# tes1.net
KiCad netlist of a schematic drawn in EAGLE
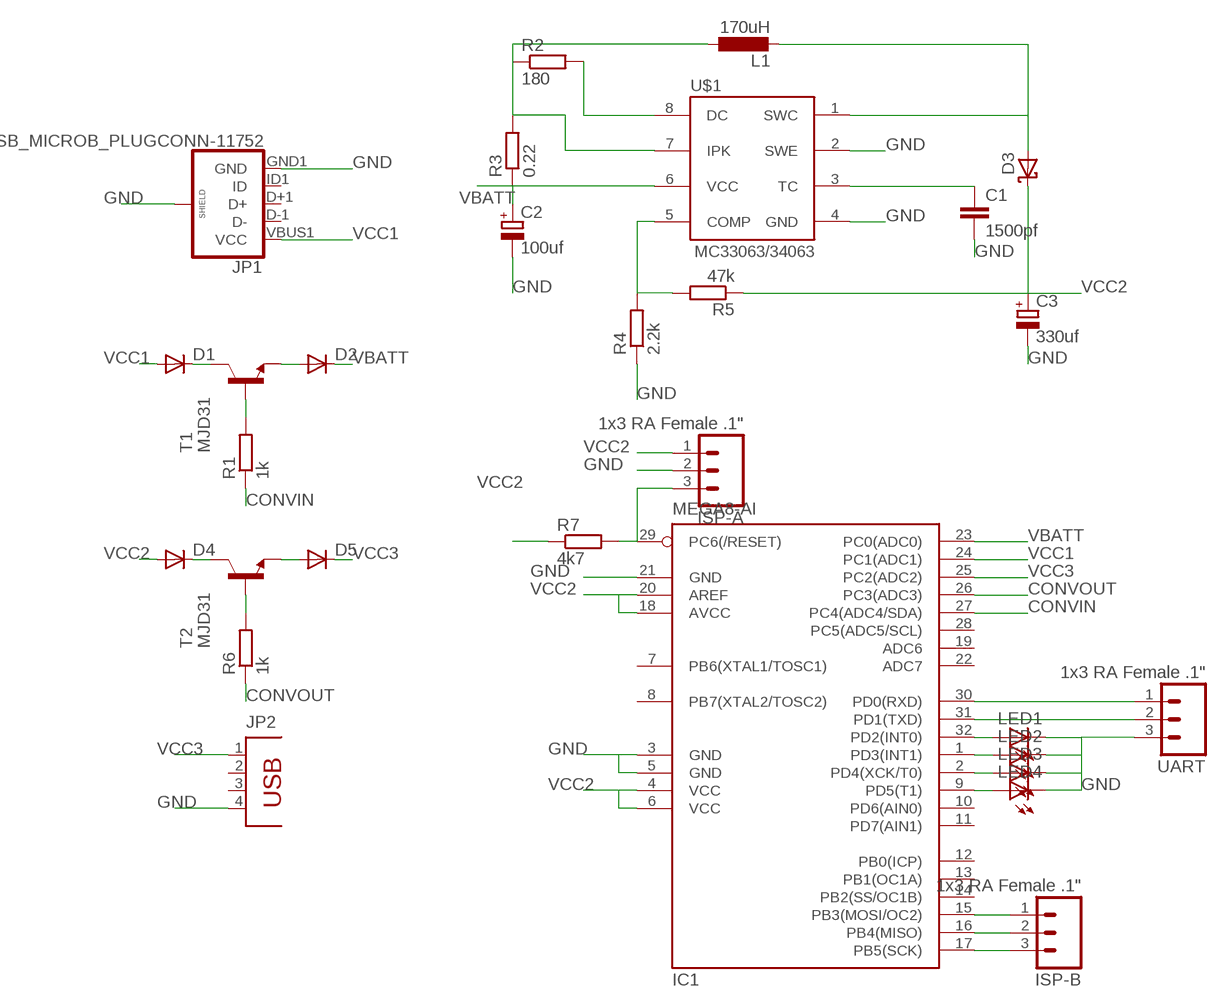
[diagram p0: schematic, sheet 1]

(export (version "E")
  (design (tool "Eeschema 10.0.6"))
  (components
    (comp (ref "C1")
      (value "1500pf")
      (footprint "eagle-import:C1206")
      (libsource (lib "eagle-import") (part "C-EUC1206"))
    )
    (comp (ref "C2")
      (value "100uf")
      (footprint "eagle-import:153CLV-1014")
      (libsource (lib "eagle-import") (part "CPOL-EU153CLV-1014"))
    )
    (comp (ref "C3")
      (value "330uf")
      (footprint "eagle-import:153CLV-1014")
      (libsource (lib "eagle-import") (part "CPOL-EU153CLV-1014"))
    )
    (comp (ref "D1")
      (value "DIODE-SMC")
      (footprint "eagle-import:SMC")
      (libsource (lib "eagle-import") (part "DIODE-SMC"))
    )
    (comp (ref "D2")
      (value "DIODE-SMC")
      (footprint "eagle-import:SMC")
      (libsource (lib "eagle-import") (part "DIODE-SMC"))
    )
    (comp (ref "D3")
      (value "SCHOTTKY-DIODEF126Z12")
      (footprint "eagle-import:F126Z12")
      (libsource (lib "eagle-import") (part "SCHOTTKY-DIODEF126Z12"))
    )
    (comp (ref "D4")
      (value "DIODE-SMC")
      (footprint "eagle-import:SMC")
      (libsource (lib "eagle-import") (part "DIODE-SMC"))
    )
    (comp (ref "D5")
      (value "DIODE-SMC")
      (footprint "eagle-import:SMC")
      (libsource (lib "eagle-import") (part "DIODE-SMC"))
    )
    (comp (ref "IC1")
      (value "MEGA8-AI")
      (footprint "eagle-import:TQFP32-08")
      (fields (field (name "MPN") "ATMEGA8-16AU"))
      (libsource (lib "eagle-import") (part "MEGA8-AI"))
    )
    (comp (ref "ISP-A")
      (value "1x3 RA Female .1\"")
      (footprint "eagle-import:1X03_SMD_RA_FEMALE")
      (libsource (lib "eagle-import") (part "M03SMD_RA_FEMALE"))
    )
    (comp (ref "ISP-B")
      (value "1x3 RA Female .1\"")
      (footprint "eagle-import:1X03_SMD_RA_FEMALE")
      (libsource (lib "eagle-import") (part "M03SMD_RA_FEMALE"))
    )
    (comp (ref "JP1")
      (value "USB_MICROB_PLUGCONN-11752")
      (footprint "eagle-import:USB-B-MICRO-SMD_V03")
      (libsource (lib "eagle-import") (part "USB_MICROB_PLUGCONN-11752"))
    )
    (comp (ref "JP2")
      (value "PN87520")
      (footprint "eagle-import:PN87520")
      (libsource (lib "eagle-import") (part "PN87520"))
    )
    (comp (ref "L1")
      (value "170uH")
      (footprint "eagle-import:L5650M")
      (libsource (lib "eagle-import") (part "L-EUL5650M"))
    )
    (comp (ref "LED1")
      (value "LEDSML1206")
      (footprint "eagle-import:SML1206")
      (libsource (lib "eagle-import") (part "LEDSML1206"))
    )
    (comp (ref "LED2")
      (value "LEDSML1206")
      (footprint "eagle-import:SML1206")
      (libsource (lib "eagle-import") (part "LEDSML1206"))
    )
    (comp (ref "LED3")
      (value "LEDSML1206")
      (footprint "eagle-import:SML1206")
      (libsource (lib "eagle-import") (part "LEDSML1206"))
    )
    (comp (ref "LED4")
      (value "LEDSML1206")
      (footprint "eagle-import:SML1206")
      (libsource (lib "eagle-import") (part "LEDSML1206"))
    )
    (comp (ref "R1")
      (value "1k")
      (footprint "eagle-import:R1206")
      (libsource (lib "eagle-import") (part "R-EU_R1206"))
    )
    (comp (ref "R2")
      (value "180")
      (footprint "eagle-import:R1206")
      (libsource (lib "eagle-import") (part "resistor_R-EU_R1206"))
    )
    (comp (ref "R3")
      (value "0.22")
      (footprint "eagle-import:R1206")
      (libsource (lib "eagle-import") (part "resistor_R-EU_R1206"))
    )
    (comp (ref "R4")
      (value "2.2k")
      (footprint "eagle-import:R1206")
      (libsource (lib "eagle-import") (part "resistor_R-EU_R1206"))
    )
    (comp (ref "R5")
      (value "47k")
      (footprint "eagle-import:R1206")
      (libsource (lib "eagle-import") (part "resistor_R-EU_R1206"))
    )
    (comp (ref "R6")
      (value "1k")
      (footprint "eagle-import:R1206")
      (libsource (lib "eagle-import") (part "R-EU_R1206"))
    )
    (comp (ref "R7")
      (value "4k7")
      (footprint "eagle-import:R1206")
      (libsource (lib "eagle-import") (part "R-EU_R1206"))
    )
    (comp (ref "T1")
      (value "MJD31")
      (footprint "eagle-import:DPAK")
      (libsource (lib "eagle-import") (part "MJD31"))
    )
    (comp (ref "T2")
      (value "MJD31")
      (footprint "eagle-import:DPAK")
      (libsource (lib "eagle-import") (part "MJD31"))
    )
    (comp (ref "U$1")
      (value "MC33063/MC34063D")
      (footprint "eagle-import:SO08")
      (libsource (lib "eagle-import") (part "MC33063/MC34063D"))
    )
    (comp (ref "UART")
      (value "1x3 RA Female .1\"")
      (footprint "eagle-import:1X03_SMD_RA_FEMALE")
      (libsource (lib "eagle-import") (part "M03SMD_RA_FEMALE"))
    )
  )
  (nets
    (net (code "1") (name "/CONVIN") (class "Default")
      (node (ref "IC1") (pin "27") (pinfunction "PC4(ADC4/SDA)_27") (pintype "bidirectional"))
      (node (ref "R1") (pin "1") (pinfunction "1_1") (pintype "passive"))
    )
    (net (code "2") (name "/CONVOUT") (class "Default")
      (node (ref "IC1") (pin "26") (pinfunction "PC3(ADC3)_26") (pintype "bidirectional"))
      (node (ref "R6") (pin "1") (pinfunction "1_1") (pintype "passive"))
    )
    (net (code "3") (name "/GND") (class "Default")
      (node (ref "C1") (pin "2") (pinfunction "2_2") (pintype "passive"))
      (node (ref "C2") (pin "-") (pinfunction "-_-") (pintype "passive"))
      (node (ref "C3") (pin "-") (pinfunction "-_-") (pintype "passive"))
      (node (ref "IC1") (pin "21") (pinfunction "GND_21") (pintype "power_in"))
      (node (ref "IC1") (pin "3") (pinfunction "GND_3") (pintype "power_in"))
      (node (ref "IC1") (pin "5") (pinfunction "GND_5") (pintype "power_in"))
      (node (ref "ISP-A") (pin "2") (pinfunction "2_2") (pintype "passive"))
      (node (ref "JP1") (pin "GND1") (pinfunction "GND_GND1") (pintype "bidirectional"))
      (node (ref "JP1") (pin "SHIELD1") (pinfunction "SHIELD_SHIELD1") (pintype "bidirectional"))
      (node (ref "JP1") (pin "SHIELD2") (pinfunction "SHIELD_SHIELD2") (pintype "bidirectional"))
      (node (ref "JP1") (pin "SHIELD3") (pinfunction "SHIELD_SHIELD3") (pintype "bidirectional"))
      (node (ref "JP2") (pin "4") (pinfunction "4_4") (pintype "passive"))
      (node (ref "LED1") (pin "C") (pinfunction "C_C") (pintype "passive"))
      (node (ref "LED2") (pin "C") (pinfunction "C_C") (pintype "passive"))
      (node (ref "LED3") (pin "C") (pinfunction "C_C") (pintype "passive"))
      (node (ref "LED4") (pin "C") (pinfunction "C_C") (pintype "passive"))
      (node (ref "R4") (pin "1") (pinfunction "1_1") (pintype "passive"))
      (node (ref "U$1") (pin "2") (pinfunction "SWE_2") (pintype "input"))
      (node (ref "U$1") (pin "4") (pinfunction "GND_4") (pintype "power_in"))
      (node (ref "UART") (pin "3") (pinfunction "3_3") (pintype "passive"))
    )
    (net (code "4") (name "/VBATT") (class "Default")
      (node (ref "C2") (pin "+") (pinfunction "+_+") (pintype "passive"))
      (node (ref "D2") (pin "C") (pinfunction "C_C") (pintype "passive"))
      (node (ref "IC1") (pin "23") (pinfunction "PC0(ADC0)_23") (pintype "bidirectional"))
      (node (ref "R3") (pin "1") (pinfunction "1_1") (pintype "passive"))
      (node (ref "U$1") (pin "6") (pinfunction "VCC_6") (pintype "power_in"))
    )
    (net (code "5") (name "/VCC1") (class "Default")
      (node (ref "D1") (pin "A") (pinfunction "A_A") (pintype "passive"))
      (node (ref "IC1") (pin "24") (pinfunction "PC1(ADC1)_24") (pintype "bidirectional"))
      (node (ref "JP1") (pin "VBUS1") (pinfunction "VCC_VBUS1") (pintype "bidirectional"))
    )
    (net (code "6") (name "/VCC2") (class "Default")
      (node (ref "C3") (pin "+") (pinfunction "+_+") (pintype "passive"))
      (node (ref "D3") (pin "C") (pinfunction "C_C") (pintype "passive"))
      (node (ref "D4") (pin "A") (pinfunction "A_A") (pintype "passive"))
      (node (ref "IC1") (pin "18") (pinfunction "AVCC_18") (pintype "power_in"))
      (node (ref "IC1") (pin "20") (pinfunction "AREF_20") (pintype "passive"))
      (node (ref "IC1") (pin "4") (pinfunction "VCC_4") (pintype "power_in"))
      (node (ref "IC1") (pin "6") (pinfunction "VCC_6") (pintype "power_in"))
      (node (ref "ISP-A") (pin "1") (pinfunction "1_1") (pintype "passive"))
      (node (ref "R5") (pin "1") (pinfunction "1_1") (pintype "passive"))
      (node (ref "R7") (pin "1") (pinfunction "1_1") (pintype "passive"))
    )
    (net (code "7") (name "/VCC3") (class "Default")
      (node (ref "D5") (pin "C") (pinfunction "C_C") (pintype "passive"))
      (node (ref "IC1") (pin "25") (pinfunction "PC2(ADC2)_25") (pintype "bidirectional"))
      (node (ref "JP2") (pin "1") (pinfunction "1_1") (pintype "passive"))
    )
    (net (code "8") (name "Net-(IC1-PB3(MOSI{slash}OC2))") (class "Default")
      (node (ref "IC1") (pin "15") (pinfunction "PB3(MOSI/OC2)_15") (pintype "bidirectional"))
      (node (ref "ISP-B") (pin "1") (pinfunction "1_1") (pintype "passive"))
    )
    (net (code "9") (name "Net-(IC1-PB4(MISO))") (class "Default")
      (node (ref "IC1") (pin "16") (pinfunction "PB4(MISO)_16") (pintype "bidirectional"))
      (node (ref "ISP-B") (pin "2") (pinfunction "2_2") (pintype "passive"))
    )
    (net (code "10") (name "Net-(IC1-PB5(SCK))") (class "Default")
      (node (ref "IC1") (pin "17") (pinfunction "PB5(SCK)_17") (pintype "bidirectional"))
      (node (ref "ISP-B") (pin "3") (pinfunction "3_3") (pintype "passive"))
    )
    (net (code "11") (name "Net-(IC1-PC6({slash}RESET))") (class "Default")
      (node (ref "IC1") (pin "29") (pinfunction "PC6(/RESET)_29") (pintype "bidirectional"))
      (node (ref "ISP-A") (pin "3") (pinfunction "3_3") (pintype "passive"))
      (node (ref "R7") (pin "2") (pinfunction "2_2") (pintype "passive"))
    )
    (net (code "12") (name "Net-(IC1-PD0(RXD))") (class "Default")
      (node (ref "IC1") (pin "30") (pinfunction "PD0(RXD)_30") (pintype "bidirectional"))
      (node (ref "UART") (pin "1") (pinfunction "1_1") (pintype "passive"))
    )
    (net (code "13") (name "Net-(IC1-PD1(TXD))") (class "Default")
      (node (ref "IC1") (pin "31") (pinfunction "PD1(TXD)_31") (pintype "bidirectional"))
      (node (ref "UART") (pin "2") (pinfunction "2_2") (pintype "passive"))
    )
    (net (code "14") (name "Net-(IC1-PD2(INT0))") (class "Default")
      (node (ref "IC1") (pin "32") (pinfunction "PD2(INT0)_32") (pintype "bidirectional"))
      (node (ref "LED1") (pin "A") (pinfunction "A_A") (pintype "passive"))
    )
    (net (code "15") (name "Net-(IC1-PD3(INT1))") (class "Default")
      (node (ref "IC1") (pin "1") (pinfunction "PD3(INT1)_1") (pintype "bidirectional"))
      (node (ref "LED2") (pin "A") (pinfunction "A_A") (pintype "passive"))
    )
    (net (code "16") (name "Net-(IC1-PD4(XCK{slash}T0))") (class "Default")
      (node (ref "IC1") (pin "2") (pinfunction "PD4(XCK/T0)_2") (pintype "bidirectional"))
      (node (ref "LED3") (pin "A") (pinfunction "A_A") (pintype "passive"))
    )
    (net (code "17") (name "Net-(IC1-PD5(T1))") (class "Default")
      (node (ref "IC1") (pin "9") (pinfunction "PD5(T1)_9") (pintype "bidirectional"))
      (node (ref "LED4") (pin "A") (pinfunction "A_A") (pintype "passive"))
    )
    (net (code "18") (name "Net-(T1-B)") (class "Default")
      (node (ref "R1") (pin "2") (pinfunction "2_2") (pintype "passive"))
      (node (ref "T1") (pin "1") (pinfunction "B_1") (pintype "passive"))
    )
    (net (code "19") (name "Net-(T1-C)") (class "Default")
      (node (ref "D1") (pin "C") (pinfunction "C_C") (pintype "passive"))
      (node (ref "T1") (pin "4") (pinfunction "C_4") (pintype "passive"))
    )
    (net (code "20") (name "Net-(T1-E)") (class "Default")
      (node (ref "D2") (pin "A") (pinfunction "A_A") (pintype "passive"))
      (node (ref "T1") (pin "3") (pinfunction "E_3") (pintype "passive"))
    )
    (net (code "21") (name "Net-(T2-B)") (class "Default")
      (node (ref "R6") (pin "2") (pinfunction "2_2") (pintype "passive"))
      (node (ref "T2") (pin "1") (pinfunction "B_1") (pintype "passive"))
    )
    (net (code "22") (name "Net-(T2-C)") (class "Default")
      (node (ref "D4") (pin "C") (pinfunction "C_C") (pintype "passive"))
      (node (ref "T2") (pin "4") (pinfunction "C_4") (pintype "passive"))
    )
    (net (code "23") (name "Net-(T2-E)") (class "Default")
      (node (ref "D5") (pin "A") (pinfunction "A_A") (pintype "passive"))
      (node (ref "T2") (pin "3") (pinfunction "E_3") (pintype "passive"))
    )
    (net (code "24") (name "Net-(U$1-COMP)") (class "Default")
      (node (ref "R4") (pin "2") (pinfunction "2_2") (pintype "passive"))
      (node (ref "R5") (pin "2") (pinfunction "2_2") (pintype "passive"))
      (node (ref "U$1") (pin "5") (pinfunction "COMP_5") (pintype "input"))
    )
    (net (code "25") (name "Net-(U$1-DC)") (class "Default")
      (node (ref "R2") (pin "2") (pinfunction "2_2") (pintype "passive"))
      (node (ref "U$1") (pin "8") (pinfunction "DC_8") (pintype "input"))
    )
    (net (code "26") (name "Net-(U$1-IPK)") (class "Default")
      (node (ref "L1") (pin "1") (pinfunction "1_1") (pintype "passive"))
      (node (ref "R2") (pin "1") (pinfunction "1_1") (pintype "passive"))
      (node (ref "R3") (pin "2") (pinfunction "2_2") (pintype "passive"))
      (node (ref "U$1") (pin "7") (pinfunction "IPK_7") (pintype "bidirectional"))
    )
    (net (code "27") (name "Net-(U$1-SWC)") (class "Default")
      (node (ref "D3") (pin "A") (pinfunction "A_A") (pintype "passive"))
      (node (ref "L1") (pin "2") (pinfunction "2_2") (pintype "passive"))
      (node (ref "U$1") (pin "1") (pinfunction "SWC_1") (pintype "input"))
    )
    (net (code "28") (name "Net-(U$1-TC)") (class "Default")
      (node (ref "C1") (pin "1") (pinfunction "1_1") (pintype "passive"))
      (node (ref "U$1") (pin "3") (pinfunction "TC_3") (pintype "input"))
    )
    (net (code "29") (name "unconnected-(IC1-ADC6-Pad19)") (class "Default")
      (node (ref "IC1") (pin "19") (pinfunction "ADC6_19") (pintype "bidirectional"))
    )
    (net (code "30") (name "unconnected-(IC1-ADC7-Pad22)") (class "Default")
      (node (ref "IC1") (pin "22") (pinfunction "ADC7_22") (pintype "bidirectional"))
    )
    (net (code "31") (name "unconnected-(IC1-PB0(ICP)-Pad12)") (class "Default")
      (node (ref "IC1") (pin "12") (pinfunction "PB0(ICP)_12") (pintype "bidirectional"))
    )
    (net (code "32") (name "unconnected-(IC1-PB1(OC1A)-Pad13)") (class "Default")
      (node (ref "IC1") (pin "13") (pinfunction "PB1(OC1A)_13") (pintype "bidirectional"))
    )
    (net (code "33") (name "unconnected-(IC1-PB2(SS{slash}OC1B)-Pad14)") (class "Default")
      (node (ref "IC1") (pin "14") (pinfunction "PB2(SS/OC1B)_14") (pintype "bidirectional"))
    )
    (net (code "34") (name "unconnected-(IC1-PB6(XTAL1{slash}TOSC1)-Pad7)") (class "Default")
      (node (ref "IC1") (pin "7") (pinfunction "PB6(XTAL1/TOSC1)_7") (pintype "bidirectional"))
    )
    (net (code "35") (name "unconnected-(IC1-PB7(XTAL2{slash}TOSC2)-Pad8)") (class "Default")
      (node (ref "IC1") (pin "8") (pinfunction "PB7(XTAL2/TOSC2)_8") (pintype "bidirectional"))
    )
    (net (code "36") (name "unconnected-(IC1-PC5(ADC5{slash}SCL)-Pad28)") (class "Default")
      (node (ref "IC1") (pin "28") (pinfunction "PC5(ADC5/SCL)_28") (pintype "bidirectional"))
    )
    (net (code "37") (name "unconnected-(IC1-PD6(AIN0)-Pad10)") (class "Default")
      (node (ref "IC1") (pin "10") (pinfunction "PD6(AIN0)_10") (pintype "bidirectional"))
    )
    (net (code "38") (name "unconnected-(IC1-PD7(AIN1)-Pad11)") (class "Default")
      (node (ref "IC1") (pin "11") (pinfunction "PD7(AIN1)_11") (pintype "bidirectional"))
    )
    (net (code "39") (name "unconnected-(JP1-D+-PadD+1)") (class "Default")
      (node (ref "JP1") (pin "D+1") (pinfunction "D+_D+1") (pintype "bidirectional"))
    )
    (net (code "40") (name "unconnected-(JP1-D--PadD-1)") (class "Default")
      (node (ref "JP1") (pin "D-1") (pinfunction "D-_D-1") (pintype "bidirectional"))
    )
    (net (code "41") (name "unconnected-(JP1-ID-PadID1)") (class "Default")
      (node (ref "JP1") (pin "ID1") (pinfunction "ID_ID1") (pintype "bidirectional"))
    )
    (net (code "42") (name "unconnected-(JP2-Pad2)") (class "Default")
      (node (ref "JP2") (pin "2") (pinfunction "2_2") (pintype "passive"))
    )
    (net (code "43") (name "unconnected-(JP2-Pad3)") (class "Default")
      (node (ref "JP2") (pin "3") (pinfunction "3_3") (pintype "passive"))
    )
  )
)
